# valve.net
KiCad netlist of a schematic drawn in Altium Designer
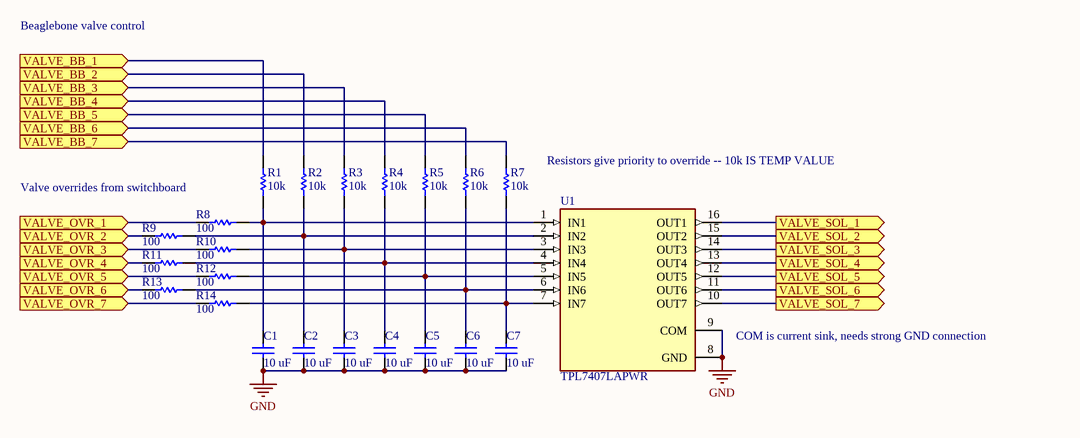
[diagram p0: valve.SchDoc]

(export (version "E")
  (design (tool "Eeschema 10.0.6"))
  (components
    (comp (ref "C1")
      (value "10 uF")
      (footprint "C0805")
      (description "0805 Capacitor")
      (libsource (lib "PARSEC") (part "C0805"))
    )
    (comp (ref "C2")
      (value "10 uF")
      (footprint "C0805")
      (description "0805 Capacitor")
      (libsource (lib "PARSEC") (part "C0805"))
    )
    (comp (ref "C3")
      (value "10 uF")
      (footprint "C0805")
      (description "0805 Capacitor")
      (libsource (lib "PARSEC") (part "C0805"))
    )
    (comp (ref "C4")
      (value "10 uF")
      (footprint "C0805")
      (description "0805 Capacitor")
      (libsource (lib "PARSEC") (part "C0805"))
    )
    (comp (ref "C5")
      (value "10 uF")
      (footprint "C0805")
      (description "0805 Capacitor")
      (libsource (lib "PARSEC") (part "C0805"))
    )
    (comp (ref "C6")
      (value "10 uF")
      (footprint "C0805")
      (description "0805 Capacitor")
      (libsource (lib "PARSEC") (part "C0805"))
    )
    (comp (ref "C7")
      (value "10 uF")
      (footprint "C0805")
      (description "0805 Capacitor")
      (libsource (lib "PARSEC") (part "C0805"))
    )
    (comp (ref "R1")
      (value "10k")
      (footprint "R0603")
      (description "RESISTOR 0603")
      (libsource (lib "PARSEC") (part "R0603"))
    )
    (comp (ref "R2")
      (value "10k")
      (footprint "R0603")
      (description "RESISTOR 0603")
      (libsource (lib "PARSEC") (part "R0603"))
    )
    (comp (ref "R3")
      (value "10k")
      (footprint "R0603")
      (description "RESISTOR 0603")
      (libsource (lib "PARSEC") (part "R0603"))
    )
    (comp (ref "R4")
      (value "10k")
      (footprint "R0603")
      (description "RESISTOR 0603")
      (libsource (lib "PARSEC") (part "R0603"))
    )
    (comp (ref "R5")
      (value "10k")
      (footprint "R0603")
      (description "RESISTOR 0603")
      (libsource (lib "PARSEC") (part "R0603"))
    )
    (comp (ref "R6")
      (value "10k")
      (footprint "R0603")
      (description "RESISTOR 0603")
      (libsource (lib "PARSEC") (part "R0603"))
    )
    (comp (ref "R7")
      (value "10k")
      (footprint "R0603")
      (description "RESISTOR 0603")
      (libsource (lib "PARSEC") (part "R0603"))
    )
    (comp (ref "R8")
      (value "100")
      (footprint "R0603")
      (description "RESISTOR 0603")
      (libsource (lib "PARSEC") (part "R0603"))
    )
    (comp (ref "R9")
      (value "100")
      (footprint "R0603")
      (description "RESISTOR 0603")
      (libsource (lib "PARSEC") (part "R0603"))
    )
    (comp (ref "R10")
      (value "100")
      (footprint "R0603")
      (description "RESISTOR 0603")
      (libsource (lib "PARSEC") (part "R0603"))
    )
    (comp (ref "R11")
      (value "100")
      (footprint "R0603")
      (description "RESISTOR 0603")
      (libsource (lib "PARSEC") (part "R0603"))
    )
    (comp (ref "R12")
      (value "100")
      (footprint "R0603")
      (description "RESISTOR 0603")
      (libsource (lib "PARSEC") (part "R0603"))
    )
    (comp (ref "R13")
      (value "100")
      (footprint "R0603")
      (description "RESISTOR 0603")
      (libsource (lib "PARSEC") (part "R0603"))
    )
    (comp (ref "R14")
      (value "100")
      (footprint "R0603")
      (description "RESISTOR 0603")
      (libsource (lib "PARSEC") (part "R0603"))
    )
    (comp (ref "U1")
      (value "TPL7407LAPWR")
      (footprint "FP-PW0016A-IPC_A")
      (description "IC PWR DRIVER N-CHAN 1:1 16TSSOP")
      (libsource (lib "Altium Content Vault") (part "acb731b2cfc92b9891b08ebdf6c22ba"))
    )
  )
  (nets
    (net (code "1") (name "/VALVE_BB_1") (class "Default")
      (node (ref "R1") (pin "1") (pinfunction "1_1") (pintype "passive"))
    )
    (net (code "2") (name "/VALVE_BB_2") (class "Default")
      (node (ref "R2") (pin "1") (pinfunction "1_1") (pintype "passive"))
    )
    (net (code "3") (name "/VALVE_BB_3") (class "Default")
      (node (ref "R3") (pin "1") (pinfunction "1_1") (pintype "passive"))
    )
    (net (code "4") (name "/VALVE_BB_4") (class "Default")
      (node (ref "R4") (pin "1") (pinfunction "1_1") (pintype "passive"))
    )
    (net (code "5") (name "/VALVE_BB_5") (class "Default")
      (node (ref "R5") (pin "1") (pinfunction "1_1") (pintype "passive"))
    )
    (net (code "6") (name "/VALVE_BB_6") (class "Default")
      (node (ref "R6") (pin "1") (pinfunction "1_1") (pintype "passive"))
    )
    (net (code "7") (name "/VALVE_BB_7") (class "Default")
      (node (ref "R7") (pin "1") (pinfunction "1_1") (pintype "passive"))
    )
    (net (code "8") (name "/VALVE_OVR_1") (class "Default")
      (node (ref "R8") (pin "2") (pinfunction "2_2") (pintype "passive"))
    )
    (net (code "9") (name "/VALVE_OVR_2") (class "Default")
      (node (ref "R9") (pin "2") (pinfunction "2_2") (pintype "passive"))
    )
    (net (code "10") (name "/VALVE_OVR_3") (class "Default")
      (node (ref "R10") (pin "2") (pinfunction "2_2") (pintype "passive"))
    )
    (net (code "11") (name "/VALVE_OVR_4") (class "Default")
      (node (ref "R11") (pin "2") (pinfunction "2_2") (pintype "passive"))
    )
    (net (code "12") (name "/VALVE_OVR_5") (class "Default")
      (node (ref "R12") (pin "2") (pinfunction "2_2") (pintype "passive"))
    )
    (net (code "13") (name "/VALVE_OVR_6") (class "Default")
      (node (ref "R13") (pin "2") (pinfunction "2_2") (pintype "passive"))
    )
    (net (code "14") (name "/VALVE_OVR_7") (class "Default")
      (node (ref "R14") (pin "2") (pinfunction "2_2") (pintype "passive"))
    )
    (net (code "15") (name "/VALVE_SOL_1") (class "Default")
      (node (ref "U1") (pin "16") (pinfunction "OUT1_16") (pintype "output"))
    )
    (net (code "16") (name "/VALVE_SOL_2") (class "Default")
      (node (ref "U1") (pin "15") (pinfunction "OUT2_15") (pintype "output"))
    )
    (net (code "17") (name "/VALVE_SOL_3") (class "Default")
      (node (ref "U1") (pin "14") (pinfunction "OUT3_14") (pintype "output"))
    )
    (net (code "18") (name "/VALVE_SOL_4") (class "Default")
      (node (ref "U1") (pin "13") (pinfunction "OUT4_13") (pintype "output"))
    )
    (net (code "19") (name "/VALVE_SOL_5") (class "Default")
      (node (ref "U1") (pin "12") (pinfunction "OUT5_12") (pintype "output"))
    )
    (net (code "20") (name "/VALVE_SOL_6") (class "Default")
      (node (ref "U1") (pin "11") (pinfunction "OUT6_11") (pintype "output"))
    )
    (net (code "21") (name "/VALVE_SOL_7") (class "Default")
      (node (ref "U1") (pin "10") (pinfunction "OUT7_10") (pintype "output"))
    )
    (net (code "22") (name "GND") (class "Default")
      (node (ref "C1") (pin "2") (pinfunction "2_2") (pintype "passive"))
      (node (ref "C2") (pin "2") (pinfunction "2_2") (pintype "passive"))
      (node (ref "C3") (pin "2") (pinfunction "2_2") (pintype "passive"))
      (node (ref "C4") (pin "2") (pinfunction "2_2") (pintype "passive"))
      (node (ref "C5") (pin "2") (pinfunction "2_2") (pintype "passive"))
      (node (ref "C6") (pin "2") (pinfunction "2_2") (pintype "passive"))
      (node (ref "C7") (pin "2") (pinfunction "2_2") (pintype "passive"))
      (node (ref "U1") (pin "8") (pinfunction "GND_8") (pintype "power_in"))
      (node (ref "U1") (pin "9") (pinfunction "COM_9") (pintype "power_in"))
    )
    (net (code "23") (name "Net-(U1-IN1)") (class "Default")
      (node (ref "C1") (pin "1") (pinfunction "1_1") (pintype "passive"))
      (node (ref "R1") (pin "2") (pinfunction "2_2") (pintype "passive"))
      (node (ref "R8") (pin "1") (pinfunction "1_1") (pintype "passive"))
      (node (ref "U1") (pin "1") (pinfunction "IN1_1") (pintype "input"))
    )
    (net (code "24") (name "Net-(U1-IN2)") (class "Default")
      (node (ref "C2") (pin "1") (pinfunction "1_1") (pintype "passive"))
      (node (ref "R2") (pin "2") (pinfunction "2_2") (pintype "passive"))
      (node (ref "R9") (pin "1") (pinfunction "1_1") (pintype "passive"))
      (node (ref "U1") (pin "2") (pinfunction "IN2_2") (pintype "input"))
    )
    (net (code "25") (name "Net-(U1-IN3)") (class "Default")
      (node (ref "C3") (pin "1") (pinfunction "1_1") (pintype "passive"))
      (node (ref "R10") (pin "1") (pinfunction "1_1") (pintype "passive"))
      (node (ref "R3") (pin "2") (pinfunction "2_2") (pintype "passive"))
      (node (ref "U1") (pin "3") (pinfunction "IN3_3") (pintype "input"))
    )
    (net (code "26") (name "Net-(U1-IN4)") (class "Default")
      (node (ref "C4") (pin "1") (pinfunction "1_1") (pintype "passive"))
      (node (ref "R11") (pin "1") (pinfunction "1_1") (pintype "passive"))
      (node (ref "R4") (pin "2") (pinfunction "2_2") (pintype "passive"))
      (node (ref "U1") (pin "4") (pinfunction "IN4_4") (pintype "input"))
    )
    (net (code "27") (name "Net-(U1-IN5)") (class "Default")
      (node (ref "C5") (pin "1") (pinfunction "1_1") (pintype "passive"))
      (node (ref "R12") (pin "1") (pinfunction "1_1") (pintype "passive"))
      (node (ref "R5") (pin "2") (pinfunction "2_2") (pintype "passive"))
      (node (ref "U1") (pin "5") (pinfunction "IN5_5") (pintype "input"))
    )
    (net (code "28") (name "Net-(U1-IN6)") (class "Default")
      (node (ref "C6") (pin "1") (pinfunction "1_1") (pintype "passive"))
      (node (ref "R13") (pin "1") (pinfunction "1_1") (pintype "passive"))
      (node (ref "R6") (pin "2") (pinfunction "2_2") (pintype "passive"))
      (node (ref "U1") (pin "6") (pinfunction "IN6_6") (pintype "input"))
    )
    (net (code "29") (name "Net-(U1-IN7)") (class "Default")
      (node (ref "C7") (pin "1") (pinfunction "1_1") (pintype "passive"))
      (node (ref "R14") (pin "1") (pinfunction "1_1") (pintype "passive"))
      (node (ref "R7") (pin "2") (pinfunction "2_2") (pintype "passive"))
      (node (ref "U1") (pin "7") (pinfunction "IN7_7") (pintype "input"))
    )
  )
)
